# adrone_v0.net
KiCad netlist of a schematic drawn in EAGLE
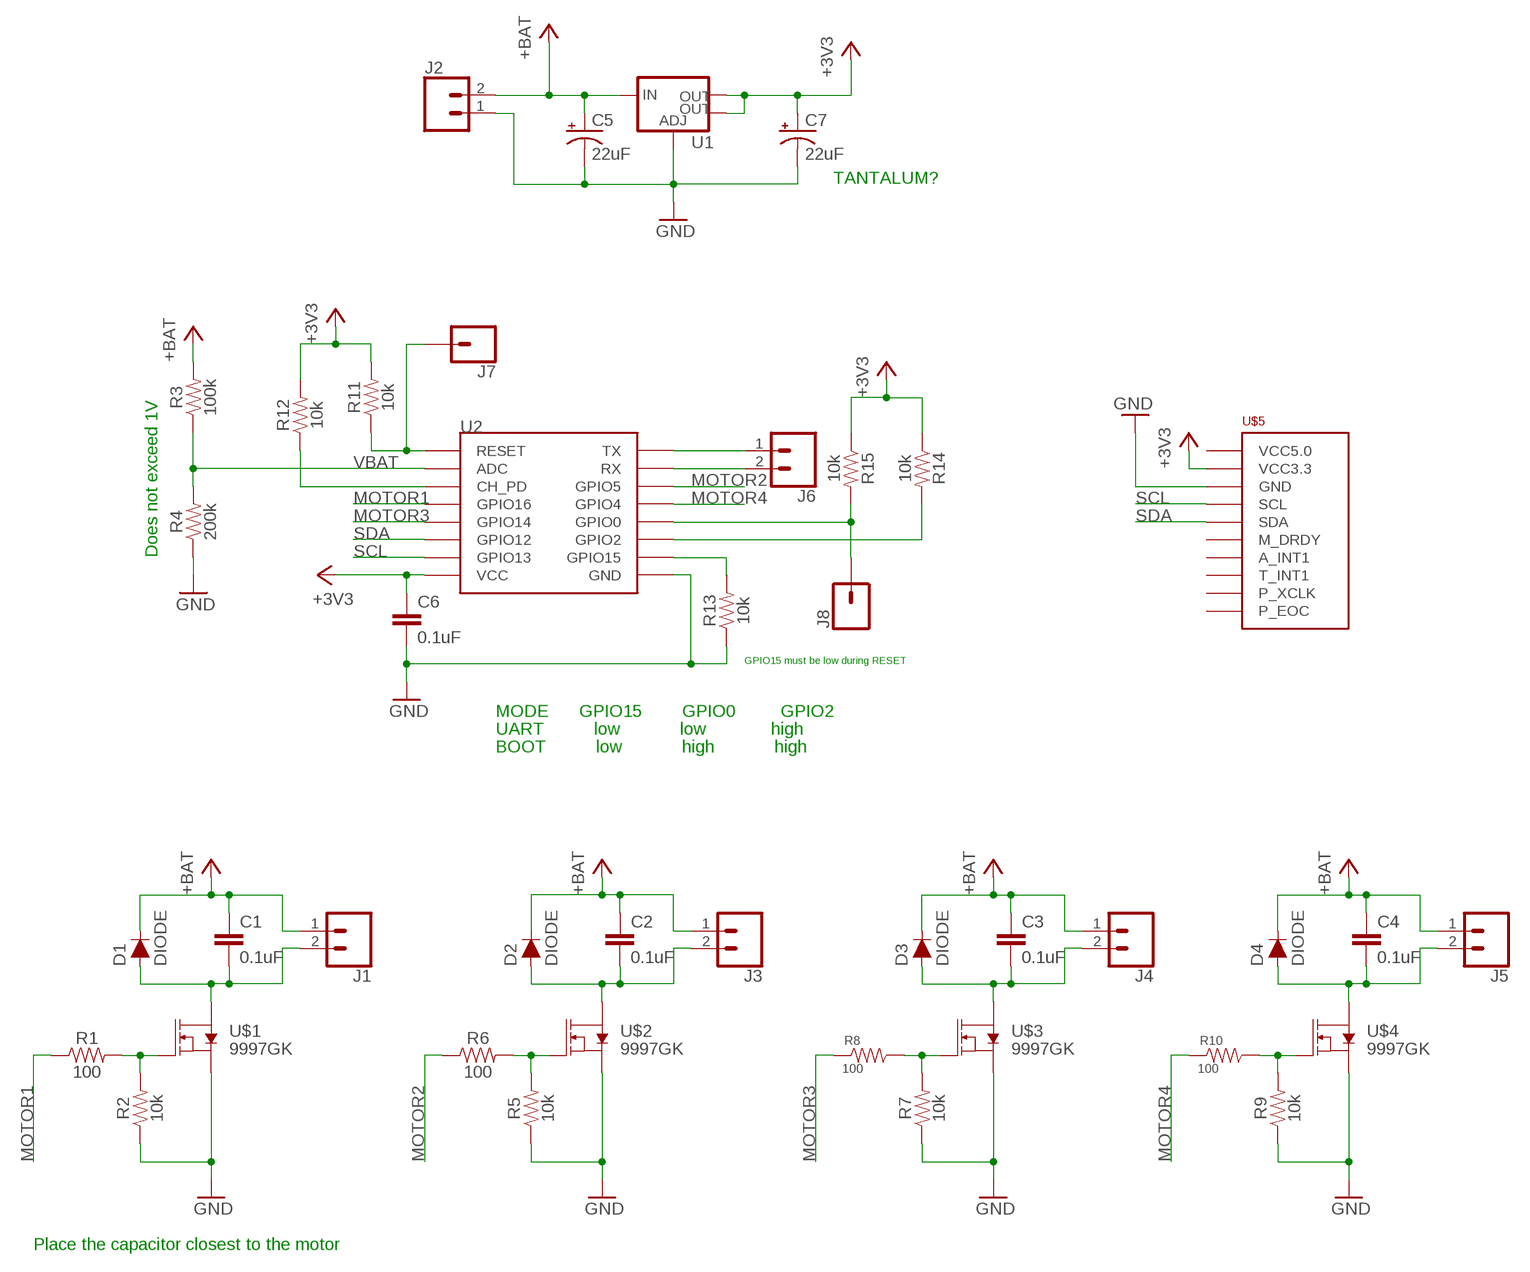
[diagram p0: schematic, sheet 1]

(export (version "E")
  (design (tool "Eeschema 10.0.6"))
  (components
    (comp (ref "C1")
      (value "0.1uF")
      (footprint "eagle-import:CAP-PTH-SMALL-KIT")
      (libsource (lib "eagle-import") (part "0.1UF-KIT-EZ-50V-20%"))
    )
    (comp (ref "C2")
      (value "0.1uF")
      (footprint "eagle-import:CAP-PTH-SMALL-KIT")
      (libsource (lib "eagle-import") (part "0.1UF-KIT-EZ-50V-20%"))
    )
    (comp (ref "C3")
      (value "0.1uF")
      (footprint "eagle-import:CAP-PTH-SMALL-KIT")
      (libsource (lib "eagle-import") (part "0.1UF-KIT-EZ-50V-20%"))
    )
    (comp (ref "C4")
      (value "0.1uF")
      (footprint "eagle-import:CAP-PTH-SMALL-KIT")
      (libsource (lib "eagle-import") (part "0.1UF-KIT-EZ-50V-20%"))
    )
    (comp (ref "C5")
      (value "22uF")
      (footprint "eagle-import:CPOL-RADIAL-2.5MM-6.5MM")
      (libsource (lib "eagle-import") (part "100UF-POLAR-RADIAL-2.5MM-25V-20%"))
    )
    (comp (ref "C6")
      (value "0.1uF")
      (footprint "eagle-import:CAP-PTH-SMALL-KIT")
      (libsource (lib "eagle-import") (part "0.1UF-KIT-EZ-50V-20%"))
    )
    (comp (ref "C7")
      (value "22uF")
      (footprint "eagle-import:CPOL-RADIAL-2.5MM-6.5MM")
      (libsource (lib "eagle-import") (part "100UF-POLAR-RADIAL-2.5MM-25V-20%"))
    )
    (comp (ref "D1")
      (value "DIODE")
      (footprint "eagle-import:AXIAL-0.1")
      (libsource (lib "eagle-import") (part "DIODE"))
    )
    (comp (ref "D2")
      (value "DIODE")
      (footprint "eagle-import:AXIAL-0.1")
      (libsource (lib "eagle-import") (part "DIODE"))
    )
    (comp (ref "D3")
      (value "DIODE")
      (footprint "eagle-import:AXIAL-0.1")
      (libsource (lib "eagle-import") (part "DIODE"))
    )
    (comp (ref "D4")
      (value "DIODE")
      (footprint "eagle-import:AXIAL-0.1")
      (libsource (lib "eagle-import") (part "DIODE"))
    )
    (comp (ref "J1")
      (value "CONN_02")
      (footprint "eagle-import:1X02")
      (libsource (lib "eagle-import") (part "CONN_02"))
    )
    (comp (ref "J2")
      (value "CONN_02")
      (footprint "eagle-import:1X02")
      (libsource (lib "eagle-import") (part "CONN_02"))
    )
    (comp (ref "J3")
      (value "CONN_02")
      (footprint "eagle-import:1X02")
      (libsource (lib "eagle-import") (part "CONN_02"))
    )
    (comp (ref "J4")
      (value "CONN_02")
      (footprint "eagle-import:1X02")
      (libsource (lib "eagle-import") (part "CONN_02"))
    )
    (comp (ref "J5")
      (value "CONN_02")
      (footprint "eagle-import:1X02")
      (libsource (lib "eagle-import") (part "CONN_02"))
    )
    (comp (ref "J6")
      (value "CONN_02")
      (footprint "eagle-import:1X02")
      (libsource (lib "eagle-import") (part "CONN_02"))
    )
    (comp (ref "J7")
      (value "CONN_01")
      (footprint "eagle-import:1X01")
      (libsource (lib "eagle-import") (part "CONN_01"))
    )
    (comp (ref "J8")
      (value "CONN_01")
      (footprint "eagle-import:1X01")
      (libsource (lib "eagle-import") (part "CONN_01"))
    )
    (comp (ref "R1")
      (value "100")
      (footprint "eagle-import:AXIAL-0.3")
      (libsource (lib "eagle-import") (part "100OHM-HORIZ-1/4W-1%"))
    )
    (comp (ref "R2")
      (value "10k")
      (footprint "eagle-import:AXIAL-0.3")
      (libsource (lib "eagle-import") (part "10KOHM-HORIZ-1/6W-5%"))
    )
    (comp (ref "R3")
      (value "100k")
      (footprint "eagle-import:AXIAL-0.3")
      (libsource (lib "eagle-import") (part "100KOHM-HORIZ-1/4W-1%"))
    )
    (comp (ref "R4")
      (value "200k")
      (footprint "eagle-import:AXIAL-0.3")
      (libsource (lib "eagle-import") (part "100KOHM-HORIZ-1/4W-5%"))
    )
    (comp (ref "R5")
      (value "10k")
      (footprint "eagle-import:AXIAL-0.3")
      (libsource (lib "eagle-import") (part "10KOHM-HORIZ-1/6W-5%"))
    )
    (comp (ref "R6")
      (value "100")
      (footprint "eagle-import:AXIAL-0.3")
      (libsource (lib "eagle-import") (part "100OHM-HORIZ-1/4W-1%"))
    )
    (comp (ref "R7")
      (value "10k")
      (footprint "eagle-import:AXIAL-0.3")
      (libsource (lib "eagle-import") (part "10KOHM-HORIZ-1/6W-5%"))
    )
    (comp (ref "R8")
      (value "100")
      (footprint "eagle-import:RES-2")
      (libsource (lib "eagle-import") (part "RES"))
    )
    (comp (ref "R9")
      (value "10k")
      (footprint "eagle-import:AXIAL-0.3")
      (libsource (lib "eagle-import") (part "10KOHM-HORIZ-1/6W-5%"))
    )
    (comp (ref "R10")
      (value "100")
      (footprint "eagle-import:RES-2")
      (libsource (lib "eagle-import") (part "RES"))
    )
    (comp (ref "R11")
      (value "10k")
      (footprint "eagle-import:AXIAL-0.3")
      (libsource (lib "eagle-import") (part "10KOHM-HORIZ-1/4W-1%"))
    )
    (comp (ref "R12")
      (value "10k")
      (footprint "eagle-import:AXIAL-0.3")
      (libsource (lib "eagle-import") (part "10KOHM-HORIZ-1/4W-1%"))
    )
    (comp (ref "R13")
      (value "10k")
      (footprint "eagle-import:AXIAL-0.1")
      (libsource (lib "eagle-import") (part "10KOHM-VERT-1/4W-1%"))
    )
    (comp (ref "R14")
      (value "10k")
      (footprint "eagle-import:AXIAL-0.3")
      (libsource (lib "eagle-import") (part "10KOHM-HORIZ-1/4W-1%"))
    )
    (comp (ref "R15")
      (value "10k")
      (footprint "eagle-import:AXIAL-0.3")
      (libsource (lib "eagle-import") (part "10KOHM-HORIZ-1/4W-1%"))
    )
    (comp (ref "U$1")
      (value "9997GK")
      (footprint "eagle-import:SOT223")
      (libsource (lib "eagle-import") (part "9997GK"))
    )
    (comp (ref "U$2")
      (value "9997GK")
      (footprint "eagle-import:SOT223")
      (libsource (lib "eagle-import") (part "9997GK"))
    )
    (comp (ref "U$3")
      (value "9997GK")
      (footprint "eagle-import:SOT223")
      (libsource (lib "eagle-import") (part "9997GK"))
    )
    (comp (ref "U$4")
      (value "9997GK")
      (footprint "eagle-import:SOT223")
      (libsource (lib "eagle-import") (part "9997GK"))
    )
    (comp (ref "U$5")
      (value "GY-80_10DOF")
      (footprint "eagle-import:GY-80_10DOF")
      (libsource (lib "eagle-import") (part "GY-80_10DOF"))
    )
    (comp (ref "U1")
      (value "V_REG_LM1117SOT223")
      (footprint "eagle-import:SOT223")
      (libsource (lib "eagle-import") (part "V_REG_LM1117SOT223"))
    )
    (comp (ref "U2")
      (value "ESP12F")
      (footprint "eagle-import:ESP12F")
      (libsource (lib "eagle-import") (part "ESP12F"))
    )
  )
  (nets
    (net (code "1") (name "+3V3") (class "Default")
      (node (ref "C6") (pin "1") (pinfunction "1_1") (pintype "passive"))
      (node (ref "C7") (pin "1") (pinfunction "+_1") (pintype "passive"))
      (node (ref "R11") (pin "P$2") (pinfunction "2_P$2") (pintype "passive"))
      (node (ref "R12") (pin "P$2") (pinfunction "2_P$2") (pintype "passive"))
      (node (ref "R14") (pin "P$1") (pinfunction "1_P$1") (pintype "passive"))
      (node (ref "R15") (pin "P$1") (pinfunction "1_P$1") (pintype "passive"))
      (node (ref "U$5") (pin "P$2") (pinfunction "VCC3.3_P$2") (pintype "bidirectional"))
      (node (ref "U1") (pin "2") (pinfunction "OUT_2") (pintype "output"))
      (node (ref "U1") (pin "4") (pinfunction "OUT_4") (pintype "output"))
      (node (ref "U2") (pin "VCC") (pinfunction "VCC_VCC") (pintype "bidirectional"))
    )
    (net (code "2") (name "+BAT") (class "Default")
      (node (ref "C1") (pin "1") (pinfunction "1_1") (pintype "passive"))
      (node (ref "C2") (pin "1") (pinfunction "1_1") (pintype "passive"))
      (node (ref "C3") (pin "1") (pinfunction "1_1") (pintype "passive"))
      (node (ref "C4") (pin "1") (pinfunction "1_1") (pintype "passive"))
      (node (ref "C5") (pin "1") (pinfunction "+_1") (pintype "passive"))
      (node (ref "D1") (pin "C") (pinfunction "C_C") (pintype "passive"))
      (node (ref "D2") (pin "C") (pinfunction "C_C") (pintype "passive"))
      (node (ref "D3") (pin "C") (pinfunction "C_C") (pintype "passive"))
      (node (ref "D4") (pin "C") (pinfunction "C_C") (pintype "passive"))
      (node (ref "J1") (pin "1") (pinfunction "1_1") (pintype "passive"))
      (node (ref "J2") (pin "2") (pinfunction "2_2") (pintype "passive"))
      (node (ref "J3") (pin "1") (pinfunction "1_1") (pintype "passive"))
      (node (ref "J4") (pin "1") (pinfunction "1_1") (pintype "passive"))
      (node (ref "J5") (pin "1") (pinfunction "1_1") (pintype "passive"))
      (node (ref "R3") (pin "P$2") (pinfunction "2_P$2") (pintype "passive"))
      (node (ref "U1") (pin "3") (pinfunction "IN_3") (pintype "input"))
    )
    (net (code "3") (name "/MOTOR1") (class "Default")
      (node (ref "R1") (pin "P$1") (pinfunction "1_P$1") (pintype "passive"))
      (node (ref "U2") (pin "GPIO16") (pinfunction "GPIO16_GPIO16") (pintype "bidirectional"))
    )
    (net (code "4") (name "/MOTOR2") (class "Default")
      (node (ref "R6") (pin "P$1") (pinfunction "1_P$1") (pintype "passive"))
      (node (ref "U2") (pin "GPIO5") (pinfunction "GPIO5_GPIO5") (pintype "bidirectional"))
    )
    (net (code "5") (name "/MOTOR3") (class "Default")
      (node (ref "R8") (pin "P$1") (pinfunction "P$1_P$1") (pintype "passive"))
      (node (ref "U2") (pin "GPIO14") (pinfunction "GPIO14_GPIO14") (pintype "bidirectional"))
    )
    (net (code "6") (name "/MOTOR4") (class "Default")
      (node (ref "R10") (pin "P$1") (pinfunction "P$1_P$1") (pintype "passive"))
      (node (ref "U2") (pin "GPIO4") (pinfunction "GPIO4_GPIO4") (pintype "bidirectional"))
    )
    (net (code "7") (name "/SCL") (class "Default")
      (node (ref "U$5") (pin "P$4") (pinfunction "SCL_P$4") (pintype "bidirectional"))
      (node (ref "U2") (pin "GPIO13") (pinfunction "GPIO13_GPIO13") (pintype "bidirectional"))
    )
    (net (code "8") (name "/SDA") (class "Default")
      (node (ref "U$5") (pin "P$5") (pinfunction "SDA_P$5") (pintype "bidirectional"))
      (node (ref "U2") (pin "GPIO12") (pinfunction "GPIO12_GPIO12") (pintype "bidirectional"))
    )
    (net (code "9") (name "/VBAT") (class "Default")
      (node (ref "R3") (pin "P$1") (pinfunction "1_P$1") (pintype "passive"))
      (node (ref "R4") (pin "P$2") (pinfunction "2_P$2") (pintype "passive"))
      (node (ref "U2") (pin "ADC") (pinfunction "ADC_ADC") (pintype "bidirectional"))
    )
    (net (code "10") (name "GND") (class "Default")
      (node (ref "C5") (pin "2") (pinfunction "-_2") (pintype "passive"))
      (node (ref "C6") (pin "2") (pinfunction "2_2") (pintype "passive"))
      (node (ref "C7") (pin "2") (pinfunction "-_2") (pintype "passive"))
      (node (ref "J2") (pin "1") (pinfunction "1_1") (pintype "passive"))
      (node (ref "R13") (pin "P$1") (pinfunction "1_P$1") (pintype "passive"))
      (node (ref "R2") (pin "P$1") (pinfunction "1_P$1") (pintype "passive"))
      (node (ref "R4") (pin "P$1") (pinfunction "1_P$1") (pintype "passive"))
      (node (ref "R5") (pin "P$1") (pinfunction "1_P$1") (pintype "passive"))
      (node (ref "R7") (pin "P$1") (pinfunction "1_P$1") (pintype "passive"))
      (node (ref "R9") (pin "P$1") (pinfunction "1_P$1") (pintype "passive"))
      (node (ref "U$1") (pin "3") (pinfunction "S_3") (pintype "bidirectional"))
      (node (ref "U$2") (pin "3") (pinfunction "S_3") (pintype "bidirectional"))
      (node (ref "U$3") (pin "3") (pinfunction "S_3") (pintype "bidirectional"))
      (node (ref "U$4") (pin "3") (pinfunction "S_3") (pintype "bidirectional"))
      (node (ref "U$5") (pin "P$3") (pinfunction "GND_P$3") (pintype "bidirectional"))
      (node (ref "U1") (pin "1") (pinfunction "ADJ_1") (pintype "input"))
      (node (ref "U2") (pin "GND") (pinfunction "GND_GND") (pintype "bidirectional"))
    )
    (net (code "11") (name "Net-(C1-Pad2)") (class "Default")
      (node (ref "C1") (pin "2") (pinfunction "2_2") (pintype "passive"))
      (node (ref "D1") (pin "A") (pinfunction "A_A") (pintype "passive"))
      (node (ref "J1") (pin "2") (pinfunction "2_2") (pintype "passive"))
      (node (ref "U$1") (pin "2") (pinfunction "D_2") (pintype "bidirectional"))
      (node (ref "U$1") (pin "4") (pinfunction "D_4") (pintype "bidirectional"))
    )
    (net (code "12") (name "Net-(C2-Pad2)") (class "Default")
      (node (ref "C2") (pin "2") (pinfunction "2_2") (pintype "passive"))
      (node (ref "D2") (pin "A") (pinfunction "A_A") (pintype "passive"))
      (node (ref "J3") (pin "2") (pinfunction "2_2") (pintype "passive"))
      (node (ref "U$2") (pin "2") (pinfunction "D_2") (pintype "bidirectional"))
      (node (ref "U$2") (pin "4") (pinfunction "D_4") (pintype "bidirectional"))
    )
    (net (code "13") (name "Net-(C3-Pad2)") (class "Default")
      (node (ref "C3") (pin "2") (pinfunction "2_2") (pintype "passive"))
      (node (ref "D3") (pin "A") (pinfunction "A_A") (pintype "passive"))
      (node (ref "J4") (pin "2") (pinfunction "2_2") (pintype "passive"))
      (node (ref "U$3") (pin "2") (pinfunction "D_2") (pintype "bidirectional"))
      (node (ref "U$3") (pin "4") (pinfunction "D_4") (pintype "bidirectional"))
    )
    (net (code "14") (name "Net-(C4-Pad2)") (class "Default")
      (node (ref "C4") (pin "2") (pinfunction "2_2") (pintype "passive"))
      (node (ref "D4") (pin "A") (pinfunction "A_A") (pintype "passive"))
      (node (ref "J5") (pin "2") (pinfunction "2_2") (pintype "passive"))
      (node (ref "U$4") (pin "2") (pinfunction "D_2") (pintype "bidirectional"))
      (node (ref "U$4") (pin "4") (pinfunction "D_4") (pintype "bidirectional"))
    )
    (net (code "15") (name "Net-(J6-Pad1)") (class "Default")
      (node (ref "J6") (pin "1") (pinfunction "1_1") (pintype "passive"))
      (node (ref "U2") (pin "TX") (pinfunction "TX_TX") (pintype "bidirectional"))
    )
    (net (code "16") (name "Net-(J6-Pad2)") (class "Default")
      (node (ref "J6") (pin "2") (pinfunction "2_2") (pintype "passive"))
      (node (ref "U2") (pin "RX") (pinfunction "RX_RX") (pintype "bidirectional"))
    )
    (net (code "17") (name "Net-(R1-2)") (class "Default")
      (node (ref "R1") (pin "P$2") (pinfunction "2_P$2") (pintype "passive"))
      (node (ref "R2") (pin "P$2") (pinfunction "2_P$2") (pintype "passive"))
      (node (ref "U$1") (pin "1") (pinfunction "G_1") (pintype "bidirectional"))
    )
    (net (code "18") (name "Net-(R5-2)") (class "Default")
      (node (ref "R5") (pin "P$2") (pinfunction "2_P$2") (pintype "passive"))
      (node (ref "R6") (pin "P$2") (pinfunction "2_P$2") (pintype "passive"))
      (node (ref "U$2") (pin "1") (pinfunction "G_1") (pintype "bidirectional"))
    )
    (net (code "19") (name "Net-(R7-2)") (class "Default")
      (node (ref "R7") (pin "P$2") (pinfunction "2_P$2") (pintype "passive"))
      (node (ref "R8") (pin "P$2") (pinfunction "P$2_P$2") (pintype "passive"))
      (node (ref "U$3") (pin "1") (pinfunction "G_1") (pintype "bidirectional"))
    )
    (net (code "20") (name "Net-(R9-2)") (class "Default")
      (node (ref "R10") (pin "P$2") (pinfunction "P$2_P$2") (pintype "passive"))
      (node (ref "R9") (pin "P$2") (pinfunction "2_P$2") (pintype "passive"))
      (node (ref "U$4") (pin "1") (pinfunction "G_1") (pintype "bidirectional"))
    )
    (net (code "21") (name "Net-(R11-1)") (class "Default")
      (node (ref "J7") (pin "1") (pinfunction "1_1") (pintype "passive"))
      (node (ref "R11") (pin "P$1") (pinfunction "1_P$1") (pintype "passive"))
      (node (ref "U2") (pin "RESET") (pinfunction "RESET_RESET") (pintype "bidirectional"))
    )
    (net (code "22") (name "Net-(R12-1)") (class "Default")
      (node (ref "R12") (pin "P$1") (pinfunction "1_P$1") (pintype "passive"))
      (node (ref "U2") (pin "CH_PD") (pinfunction "CH_PD_CH_PD") (pintype "bidirectional"))
    )
    (net (code "23") (name "Net-(R13-2)") (class "Default")
      (node (ref "R13") (pin "P$2") (pinfunction "2_P$2") (pintype "passive"))
      (node (ref "U2") (pin "GPIO15") (pinfunction "GPIO15_GPIO15") (pintype "bidirectional"))
    )
    (net (code "24") (name "Net-(R14-2)") (class "Default")
      (node (ref "R14") (pin "P$2") (pinfunction "2_P$2") (pintype "passive"))
      (node (ref "U2") (pin "GPIO2") (pinfunction "GPIO2_GPIO2") (pintype "bidirectional"))
    )
    (net (code "25") (name "Net-(R15-2)") (class "Default")
      (node (ref "J8") (pin "1") (pinfunction "1_1") (pintype "passive"))
      (node (ref "R15") (pin "P$2") (pinfunction "2_P$2") (pintype "passive"))
      (node (ref "U2") (pin "GPIO0") (pinfunction "GPIO0_GPIO0") (pintype "bidirectional"))
    )
    (net (code "26") (name "unconnected-(U$5-A_INT1-PadP$7)") (class "Default")
      (node (ref "U$5") (pin "P$7") (pinfunction "A_INT1_P$7") (pintype "bidirectional"))
    )
    (net (code "27") (name "unconnected-(U$5-M_DRDY-PadP$6)") (class "Default")
      (node (ref "U$5") (pin "P$6") (pinfunction "M_DRDY_P$6") (pintype "bidirectional"))
    )
    (net (code "28") (name "unconnected-(U$5-P_EOC-PadP$10)") (class "Default")
      (node (ref "U$5") (pin "P$10") (pinfunction "P_EOC_P$10") (pintype "bidirectional"))
    )
    (net (code "29") (name "unconnected-(U$5-P_XCLK-PadP$9)") (class "Default")
      (node (ref "U$5") (pin "P$9") (pinfunction "P_XCLK_P$9") (pintype "bidirectional"))
    )
    (net (code "30") (name "unconnected-(U$5-T_INT1-PadP$8)") (class "Default")
      (node (ref "U$5") (pin "P$8") (pinfunction "T_INT1_P$8") (pintype "bidirectional"))
    )
    (net (code "31") (name "unconnected-(U$5-VCC5.0-PadP$1)") (class "Default")
      (node (ref "U$5") (pin "P$1") (pinfunction "VCC5.0_P$1") (pintype "bidirectional"))
    )
  )
)
